# h2oiq_v2.net
KiCad netlist of a schematic drawn in EAGLE
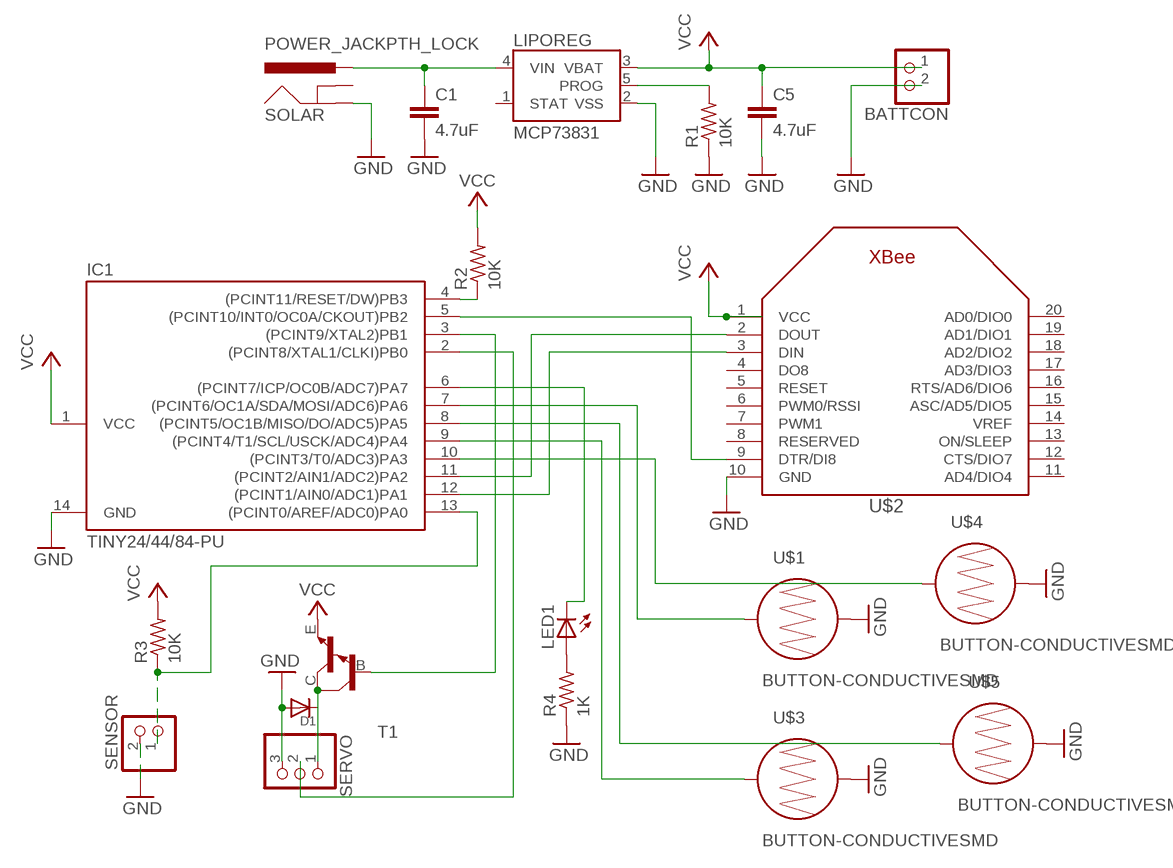
[diagram p0: schematic, sheet 1]

(export (version "E")
  (design (tool "Eeschema 10.0.6"))
  (components
    (comp (ref "BATTCON")
      (value "JST_2PIN-SMT")
      (footprint "eagle-import:JST-PH-2-SMT")
      (libsource (lib "eagle-import") (part "JST_2PIN-SMT"))
    )
    (comp (ref "C1")
      (value "4.7uF")
      (footprint "eagle-import:0402-CAP")
      (libsource (lib "eagle-import") (part "CAP0402-CAP"))
    )
    (comp (ref "C5")
      (value "4.7uF")
      (footprint "eagle-import:0402-CAP")
      (libsource (lib "eagle-import") (part "CAP0402-CAP"))
    )
    (comp (ref "D1")
      (value "DIODESMA")
      (footprint "eagle-import:SMADIODE")
      (libsource (lib "eagle-import") (part "DIODESMA"))
    )
    (comp (ref "IC1")
      (value "TINY24/44/84-PU")
      (footprint "eagle-import:DIL14")
      (libsource (lib "eagle-import") (part "TINY24/44/84-PU"))
    )
    (comp (ref "LED1")
      (value "LED5MM")
      (footprint "eagle-import:LED5MM")
      (libsource (lib "eagle-import") (part "LED5MM"))
    )
    (comp (ref "LIPOREG")
      (value "MCP73831")
      (footprint "eagle-import:SOT23-5")
      (libsource (lib "eagle-import") (part "MCP73831"))
    )
    (comp (ref "R1")
      (value "10K")
      (footprint "eagle-import:M1206")
      (libsource (lib "eagle-import") (part "R-US_M1206"))
    )
    (comp (ref "R2")
      (value "10K")
      (footprint "eagle-import:M1206")
      (libsource (lib "eagle-import") (part "R-US_M1206"))
    )
    (comp (ref "R3")
      (value "10K")
      (footprint "eagle-import:M1206")
      (libsource (lib "eagle-import") (part "R-US_M1206"))
    )
    (comp (ref "R4")
      (value "1K")
      (footprint "eagle-import:M1206")
      (libsource (lib "eagle-import") (part "R-US_M1206"))
    )
    (comp (ref "SENSOR")
      (value "JST_2PIN-SMT")
      (footprint "eagle-import:JST-PH-2-SMT")
      (libsource (lib "eagle-import") (part "JST_2PIN-SMT"))
    )
    (comp (ref "SERVO")
      (value "PINHD-1X3CB")
      (footprint "eagle-import:1X03-CLEANBIG")
      (libsource (lib "eagle-import") (part "PINHD-1X3CB"))
    )
    (comp (ref "SOLAR")
      (value "POWER_JACKPTH_LOCK")
      (footprint "eagle-import:POWER_JACK_PTH_LOCK")
      (libsource (lib "eagle-import") (part "POWER_JACKPTH_LOCK"))
    )
    (comp (ref "T1")
      (value "MMBTA13LT1-NPN_DARL-SOT23-BEC")
      (footprint "eagle-import:SOT23-BEC")
      (libsource (lib "eagle-import") (part "-NPN_DARL-SOT23-BECMMBTA13LT1"))
    )
    (comp (ref "U$1")
      (value "BUTTON-CONDUCTIVESMD")
      (footprint "eagle-import:BUTTON-CONDUCTIVE")
      (libsource (lib "eagle-import") (part "BUTTON-CONDUCTIVESMD"))
    )
    (comp (ref "U$2")
      (value "XBEE")
      (footprint "eagle-import:XBEE")
      (libsource (lib "eagle-import") (part "XBEE"))
    )
    (comp (ref "U$3")
      (value "BUTTON-CONDUCTIVESMD")
      (footprint "eagle-import:BUTTON-CONDUCTIVE")
      (libsource (lib "eagle-import") (part "BUTTON-CONDUCTIVESMD"))
    )
    (comp (ref "U$4")
      (value "BUTTON-CONDUCTIVESMD")
      (footprint "eagle-import:BUTTON-CONDUCTIVE")
      (libsource (lib "eagle-import") (part "BUTTON-CONDUCTIVESMD"))
    )
    (comp (ref "U$5")
      (value "BUTTON-CONDUCTIVESMD")
      (footprint "eagle-import:BUTTON-CONDUCTIVE")
      (libsource (lib "eagle-import") (part "BUTTON-CONDUCTIVESMD"))
    )
  )
  (nets
    (net (code "1") (name "GND") (class "Default")
      (node (ref "BATTCON") (pin "2") (pinfunction "1_2") (pintype "passive"))
      (node (ref "C1") (pin "2") (pinfunction "2_2") (pintype "passive"))
      (node (ref "C5") (pin "2") (pinfunction "2_2") (pintype "passive"))
      (node (ref "D1") (pin "A") (pinfunction "A_A") (pintype "passive"))
      (node (ref "IC1") (pin "14") (pinfunction "GND_14") (pintype "power_in"))
      (node (ref "LIPOREG") (pin "2") (pinfunction "VSS_2") (pintype "power_in"))
      (node (ref "R1") (pin "1") (pinfunction "1_1") (pintype "passive"))
      (node (ref "R4") (pin "1") (pinfunction "1_1") (pintype "passive"))
      (node (ref "SENSOR") (pin "2") (pinfunction "1_2") (pintype "passive"))
      (node (ref "SERVO") (pin "3") (pinfunction "3_3") (pintype "passive"))
      (node (ref "SOLAR") (pin "GND") (pinfunction "GND_GND") (pintype "bidirectional"))
      (node (ref "U$1") (pin "2") (pinfunction "2_2") (pintype "passive"))
      (node (ref "U$2") (pin "10") (pinfunction "GND_10") (pintype "power_in"))
      (node (ref "U$3") (pin "2") (pinfunction "2_2") (pintype "passive"))
      (node (ref "U$4") (pin "2") (pinfunction "2_2") (pintype "passive"))
      (node (ref "U$5") (pin "2") (pinfunction "2_2") (pintype "passive"))
    )
    (net (code "2") (name "Net-(D1-PadC)") (class "Default")
      (node (ref "D1") (pin "C") (pinfunction "C_C") (pintype "passive"))
      (node (ref "SERVO") (pin "1") (pinfunction "1_1") (pintype "passive"))
      (node (ref "T1") (pin "C") (pinfunction "C_C") (pintype "passive"))
    )
    (net (code "3") (name "Net-(IC1-(PCINT0{slash}AREF{slash}ADC0)PA0)") (class "Default")
      (node (ref "IC1") (pin "13") (pinfunction "(PCINT0/AREF/ADC0)PA0_13") (pintype "bidirectional"))
      (node (ref "R3") (pin "1") (pinfunction "1_1") (pintype "passive"))
      (node (ref "SENSOR") (pin "1") (pinfunction "2_1") (pintype "passive"))
    )
    (net (code "4") (name "Net-(IC1-(PCINT1{slash}AIN0{slash}ADC1)PA1)") (class "Default")
      (node (ref "IC1") (pin "12") (pinfunction "(PCINT1/AIN0/ADC1)PA1_12") (pintype "bidirectional"))
      (node (ref "U$2") (pin "3") (pinfunction "DIN_3") (pintype "input"))
    )
    (net (code "5") (name "Net-(IC1-(PCINT2{slash}AIN1{slash}ADC2)PA2)") (class "Default")
      (node (ref "IC1") (pin "11") (pinfunction "(PCINT2/AIN1/ADC2)PA2_11") (pintype "bidirectional"))
      (node (ref "U$2") (pin "2") (pinfunction "DOUT_2") (pintype "output"))
    )
    (net (code "6") (name "Net-(IC1-(PCINT3{slash}T0{slash}ADC3)PA3)") (class "Default")
      (node (ref "IC1") (pin "10") (pinfunction "(PCINT3/T0/ADC3)PA3_10") (pintype "bidirectional"))
      (node (ref "U$4") (pin "1") (pinfunction "1_1") (pintype "passive"))
    )
    (net (code "7") (name "Net-(IC1-(PCINT4{slash}T1{slash}SCL{slash}USCK{slash}ADC4)PA4)") (class "Default")
      (node (ref "IC1") (pin "9") (pinfunction "(PCINT4/T1/SCL/USCK/ADC4)PA4_9") (pintype "bidirectional"))
      (node (ref "U$3") (pin "1") (pinfunction "1_1") (pintype "passive"))
    )
    (net (code "8") (name "Net-(IC1-(PCINT5{slash}OC1B{slash}MISO{slash}DO{slash}ADC5)PA5)") (class "Default")
      (node (ref "IC1") (pin "8") (pinfunction "(PCINT5/OC1B/MISO/DO/ADC5)PA5_8") (pintype "bidirectional"))
      (node (ref "U$5") (pin "1") (pinfunction "1_1") (pintype "passive"))
    )
    (net (code "9") (name "Net-(IC1-(PCINT6{slash}OC1A{slash}SDA{slash}MOSI{slash}ADC6)PA6)") (class "Default")
      (node (ref "IC1") (pin "7") (pinfunction "(PCINT6/OC1A/SDA/MOSI/ADC6)PA6_7") (pintype "bidirectional"))
      (node (ref "U$1") (pin "1") (pinfunction "1_1") (pintype "passive"))
    )
    (net (code "10") (name "Net-(IC1-(PCINT7{slash}ICP{slash}OC0B{slash}ADC7)PA7)") (class "Default")
      (node (ref "IC1") (pin "6") (pinfunction "(PCINT7/ICP/OC0B/ADC7)PA7_6") (pintype "bidirectional"))
      (node (ref "LED1") (pin "K") (pinfunction "C_K") (pintype "passive"))
    )
    (net (code "11") (name "Net-(IC1-(PCINT8{slash}XTAL1{slash}CLKI)PB0)") (class "Default")
      (node (ref "IC1") (pin "2") (pinfunction "(PCINT8/XTAL1/CLKI)PB0_2") (pintype "bidirectional"))
      (node (ref "SERVO") (pin "2") (pinfunction "2_2") (pintype "passive"))
    )
    (net (code "12") (name "Net-(IC1-(PCINT9{slash}XTAL2)PB1)") (class "Default")
      (node (ref "IC1") (pin "3") (pinfunction "(PCINT9/XTAL2)PB1_3") (pintype "bidirectional"))
      (node (ref "T1") (pin "B") (pinfunction "B_B") (pintype "passive"))
    )
    (net (code "13") (name "Net-(IC1-(PCINT10{slash}INT0{slash}OC0A{slash}CKOUT)PB2)") (class "Default")
      (node (ref "IC1") (pin "5") (pinfunction "(PCINT10/INT0/OC0A/CKOUT)PB2_5") (pintype "bidirectional"))
      (node (ref "U$2") (pin "9") (pinfunction "DTR/DI8_9") (pintype "input"))
    )
    (net (code "14") (name "Net-(IC1-(PCINT11{slash}RESET{slash}DW)PB3)") (class "Default")
      (node (ref "IC1") (pin "4") (pinfunction "(PCINT11/RESET/DW)PB3_4") (pintype "bidirectional"))
      (node (ref "R2") (pin "1") (pinfunction "1_1") (pintype "passive"))
    )
    (net (code "15") (name "Net-(LED1-PadA)") (class "Default")
      (node (ref "LED1") (pin "A") (pinfunction "A_A") (pintype "passive"))
      (node (ref "R4") (pin "2") (pinfunction "2_2") (pintype "passive"))
    )
    (net (code "16") (name "Net-(LIPOREG-PROG)") (class "Default")
      (node (ref "LIPOREG") (pin "5") (pinfunction "PROG_5") (pintype "input"))
      (node (ref "R1") (pin "2") (pinfunction "2_2") (pintype "passive"))
    )
    (net (code "17") (name "Net-(LIPOREG-VIN)") (class "Default")
      (node (ref "C1") (pin "1") (pinfunction "1_1") (pintype "passive"))
      (node (ref "LIPOREG") (pin "4") (pinfunction "VIN_4") (pintype "power_in"))
      (node (ref "SOLAR") (pin "PWR") (pinfunction "PWR_PWR") (pintype "bidirectional"))
    )
    (net (code "18") (name "VCC") (class "Default")
      (node (ref "BATTCON") (pin "1") (pinfunction "2_1") (pintype "passive"))
      (node (ref "C5") (pin "1") (pinfunction "1_1") (pintype "passive"))
      (node (ref "IC1") (pin "1") (pinfunction "VCC_1") (pintype "power_in"))
      (node (ref "LIPOREG") (pin "3") (pinfunction "VBAT_3") (pintype "power_in"))
      (node (ref "R2") (pin "2") (pinfunction "2_2") (pintype "passive"))
      (node (ref "R3") (pin "2") (pinfunction "2_2") (pintype "passive"))
      (node (ref "T1") (pin "E") (pinfunction "E_E") (pintype "passive"))
      (node (ref "U$2") (pin "1") (pinfunction "VCC_1") (pintype "power_in"))
    )
    (net (code "19") (name "unconnected-(LIPOREG-STAT-Pad1)") (class "Default")
      (node (ref "LIPOREG") (pin "1") (pinfunction "STAT_1") (pintype "output"))
    )
    (net (code "20") (name "unconnected-(SOLAR-PadGNDBREAK)") (class "Default")
      (node (ref "SOLAR") (pin "GNDBREAK") (pinfunction "GNDBREAK_GNDBREAK") (pintype "bidirectional"))
    )
    (net (code "21") (name "unconnected-(U$2-AD0{slash}DIO0-Pad20)") (class "Default")
      (node (ref "U$2") (pin "20") (pinfunction "AD0/DIO0_20") (pintype "bidirectional"))
    )
    (net (code "22") (name "unconnected-(U$2-AD1{slash}DIO1-Pad19)") (class "Default")
      (node (ref "U$2") (pin "19") (pinfunction "AD1/DIO1_19") (pintype "bidirectional"))
    )
    (net (code "23") (name "unconnected-(U$2-AD2{slash}DIO2-Pad18)") (class "Default")
      (node (ref "U$2") (pin "18") (pinfunction "AD2/DIO2_18") (pintype "bidirectional"))
    )
    (net (code "24") (name "unconnected-(U$2-AD3{slash}DIO3-Pad17)") (class "Default")
      (node (ref "U$2") (pin "17") (pinfunction "AD3/DIO3_17") (pintype "bidirectional"))
    )
    (net (code "25") (name "unconnected-(U$2-AD4{slash}DIO4-Pad11)") (class "Default")
      (node (ref "U$2") (pin "11") (pinfunction "AD4/DIO4_11") (pintype "bidirectional"))
    )
    (net (code "26") (name "unconnected-(U$2-ASC{slash}AD5{slash}DIO5-Pad15)") (class "Default")
      (node (ref "U$2") (pin "15") (pinfunction "ASC/AD5/DIO5_15") (pintype "bidirectional"))
    )
    (net (code "27") (name "unconnected-(U$2-CTS{slash}DIO7-Pad12)") (class "Default")
      (node (ref "U$2") (pin "12") (pinfunction "CTS/DIO7_12") (pintype "bidirectional"))
    )
    (net (code "28") (name "unconnected-(U$2-DO8-Pad4)") (class "Default")
      (node (ref "U$2") (pin "4") (pinfunction "DO8_4") (pintype "output"))
    )
    (net (code "29") (name "unconnected-(U$2-ON{slash}SLEEP-Pad13)") (class "Default")
      (node (ref "U$2") (pin "13") (pinfunction "ON/SLEEP_13") (pintype "output"))
    )
    (net (code "30") (name "unconnected-(U$2-PWM0{slash}RSSI-Pad6)") (class "Default")
      (node (ref "U$2") (pin "6") (pinfunction "PWM0/RSSI_6") (pintype "output"))
    )
    (net (code "31") (name "unconnected-(U$2-PWM1-Pad7)") (class "Default")
      (node (ref "U$2") (pin "7") (pinfunction "PWM1_7") (pintype "output"))
    )
    (net (code "32") (name "unconnected-(U$2-RESERVED-Pad8)") (class "Default")
      (node (ref "U$2") (pin "8") (pinfunction "RESERVED_8") (pintype "no_connect"))
    )
    (net (code "33") (name "unconnected-(U$2-RESET-Pad5)") (class "Default")
      (node (ref "U$2") (pin "5") (pinfunction "RESET_5") (pintype "input"))
    )
    (net (code "34") (name "unconnected-(U$2-RTS{slash}AD6{slash}DIO6-Pad16)") (class "Default")
      (node (ref "U$2") (pin "16") (pinfunction "RTS/AD6/DIO6_16") (pintype "bidirectional"))
    )
    (net (code "35") (name "unconnected-(U$2-VREF-Pad14)") (class "Default")
      (node (ref "U$2") (pin "14") (pinfunction "VREF_14") (pintype "input"))
    )
  )
)
